# Aux_Lights_Daughter_REV2.net
KiCad netlist of a schematic drawn in Altium Designer
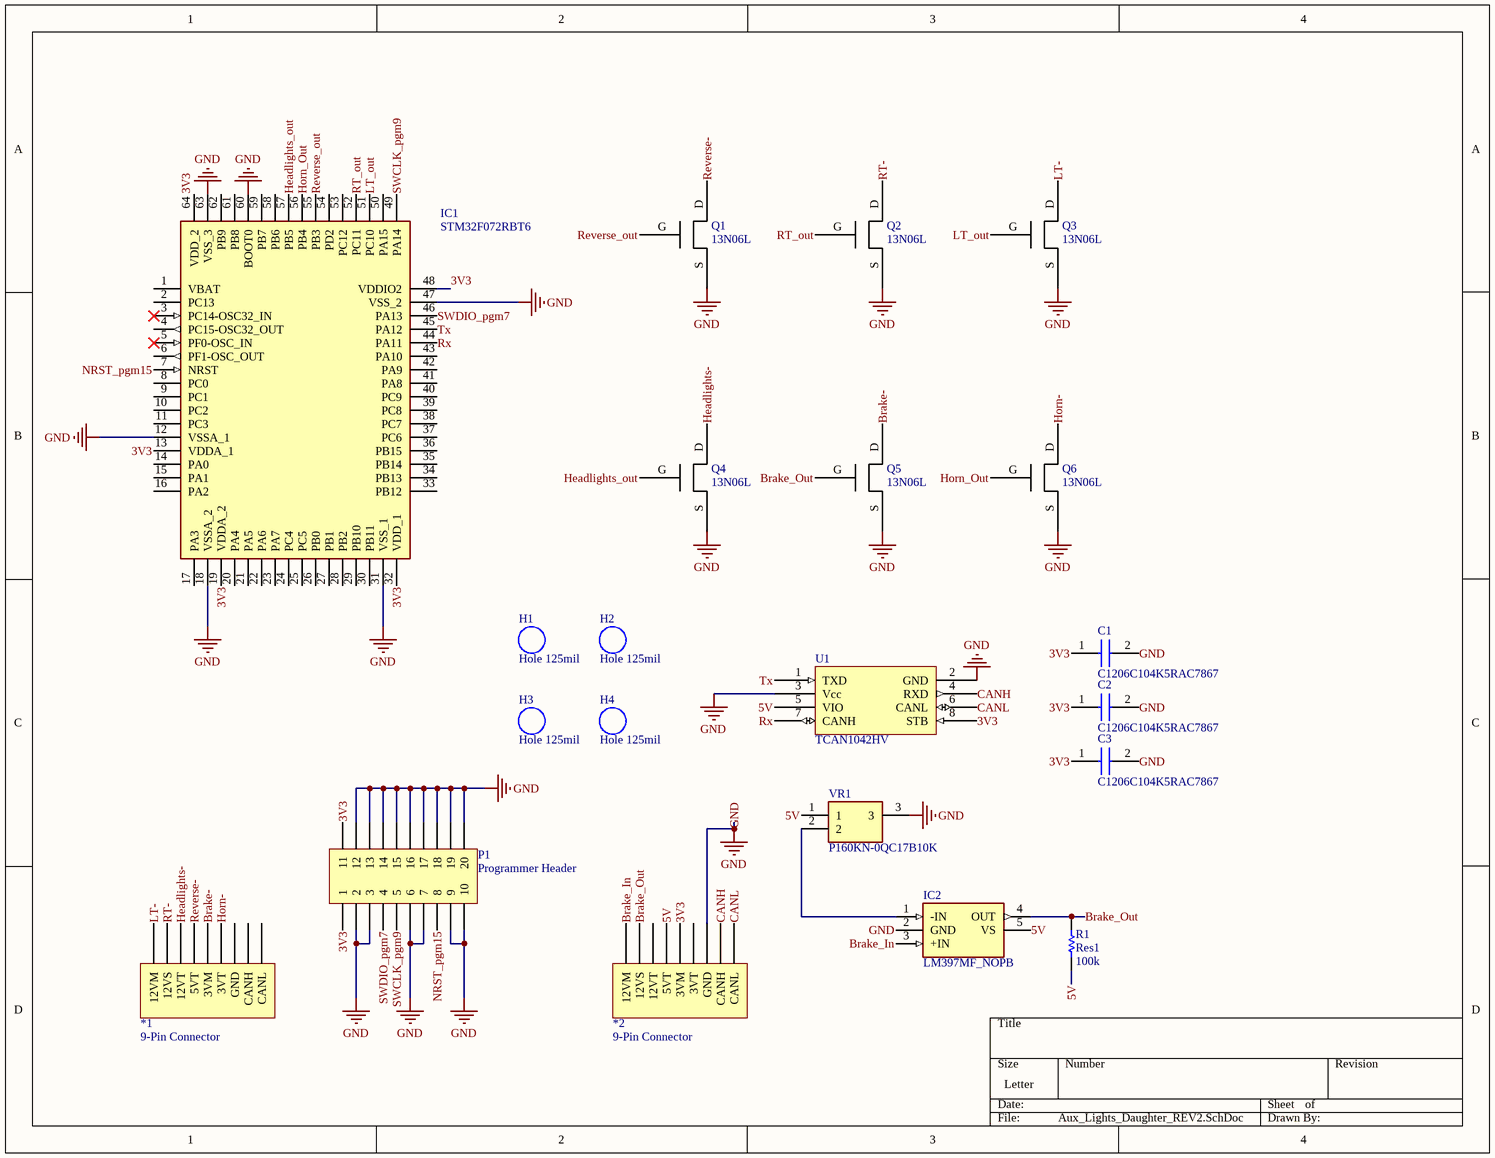
[diagram p0: Aux_Lights_Daughter_REV2.SchDoc]

(export (version "E")
  (design (tool "Eeschema 10.0.6"))
  (components
    (comp (ref "*1")
      (value "9-Pin Connector")
      (footprint "9-Pin")
      (libsource (lib "SolarGators") (part "9-Pin Connector"))
    )
    (comp (ref "*2")
      (value "9-Pin Connector")
      (footprint "9-Pin")
      (libsource (lib "SolarGators") (part "9-Pin Connector"))
    )
    (comp (ref "C1")
      (value "C1206C104K5RAC7867")
      (footprint "SamacSys:CAPC3216X110N")
      (description "Capacitor")
      (fields (field (name "MOUSER2 PART NUMBER") "80-C1206104K5RAC7867"))
      (libsource (lib "*") (part "C1206C104K5RAC7867"))
    )
    (comp (ref "C2")
      (value "C1206C104K5RAC7867")
      (footprint "SamacSys:CAPC3216X110N")
      (description "Capacitor")
      (fields (field (name "MOUSER2 PART NUMBER") "80-C1206104K5RAC7867"))
      (libsource (lib "*") (part "C1206C104K5RAC7867"))
    )
    (comp (ref "C3")
      (value "C1206C104K5RAC7867")
      (footprint "SamacSys:CAPC3216X110N")
      (description "Capacitor")
      (fields (field (name "MOUSER2 PART NUMBER") "80-C1206104K5RAC7867"))
      (libsource (lib "*") (part "C1206C104K5RAC7867"))
    )
    (comp (ref "H1")
      (value "Hole 125mil")
      (footprint "Hole 125mil")
      (libsource (lib "ECE LIB new") (part "Hole 125mil"))
    )
    (comp (ref "H2")
      (value "Hole 125mil")
      (footprint "Hole 125mil")
      (libsource (lib "ECE LIB new") (part "Hole 125mil"))
    )
    (comp (ref "H3")
      (value "Hole 125mil")
      (footprint "Hole 125mil")
      (libsource (lib "ECE LIB new") (part "Hole 125mil"))
    )
    (comp (ref "H4")
      (value "Hole 125mil")
      (footprint "Hole 125mil")
      (libsource (lib "ECE LIB new") (part "Hole 125mil"))
    )
    (comp (ref "IC1")
      (value "STM32F072RBT6")
      (footprint "QFP50P1200X1200X160-64N")
      (description "Integrated Circuit")
      (fields (field (name "MOUSER PART NUMBER") "511-STM32F072RBT6"))
      (libsource (lib "solargatorsproject") (part "STM32F072RBT6"))
    )
    (comp (ref "IC2")
      (value "LM397MF_NOPB")
      (footprint "SamacSys:SOT95P280X145-5N")
      (description "Integrated Circuit")
      (fields
        (field (name "MOUSER PART NUMBER") "926-LM397MF/NOPB")
        (field (name "MANUFACTURER_PART_NUMBER") "LM397MF/NOPB")
      )
      (libsource (lib "*") (part "LM397MF_NOPB"))
    )
    (comp (ref "P1")
      (value "Programmer Header")
      (footprint "HDR2X10_CEN")
      (description "Header, 10-Pin, Dual row")
      (fields (field (name "PUBLISHER") "Altium Limited"))
      (libsource (lib "Miscellaneous Connectors") (part "Header 10X2A"))
    )
    (comp (ref "Q1") (value "13N06L") (footprint "13N06L") (libsource (lib "SolarGators") (part "13N06L")))
    (comp (ref "Q2") (value "13N06L") (footprint "13N06L") (libsource (lib "SolarGators") (part "13N06L")))
    (comp (ref "Q3") (value "13N06L") (footprint "13N06L") (libsource (lib "SolarGators") (part "13N06L")))
    (comp (ref "Q4") (value "13N06L") (footprint "13N06L") (libsource (lib "SolarGators") (part "13N06L")))
    (comp (ref "Q5") (value "13N06L") (footprint "13N06L") (libsource (lib "SolarGators") (part "13N06L")))
    (comp (ref "Q6") (value "13N06L") (footprint "13N06L") (libsource (lib "SolarGators") (part "13N06L")))
    (comp (ref "R1")
      (value "Res1")
      (footprint "AXIAL-0.3")
      (description "Resistor")
      (fields (field (name "ALTIUM_VALUE") "100k") (field (name "PUBLISHER") "Altium Limited"))
      (libsource (lib "Miscellaneous Devices") (part "Res1"))
    )
    (comp (ref "U1")
      (value "TCAN1042HV")
      (footprint "CANIC")
      (description "TCAN1042Fault ProtectedCAN Transceiverwith CAN FD")
      (libsource (lib "Schlib1") (part "TCAN1042HV"))
    )
    (comp (ref "VR1")
      (value "P160KN-0QC17B10K")
      (footprint "POT inline wide")
      (description "Variable Resistor")
      (fields (field (name "MOUSER PART NUMBER") "858-P160KN-OQC17B10K"))
      (libsource (lib "*") (part "P160KN-0QC17B10K"))
    )
  )
  (nets
    (net (code "1") (name "/3V3") (class "Default")
      (node (ref "*2") (pin "5") (pinfunction "3VM_5") (pintype "passive"))
      (node (ref "C1") (pin "1") (pinfunction "1_1") (pintype "passive"))
      (node (ref "C2") (pin "1") (pinfunction "1_1") (pintype "passive"))
      (node (ref "C3") (pin "1") (pinfunction "1_1") (pintype "passive"))
      (node (ref "IC1") (pin "13") (pinfunction "VDDA_1_13") (pintype "power_in"))
      (node (ref "IC1") (pin "19") (pinfunction "VDDA_2_19") (pintype "power_in"))
      (node (ref "IC1") (pin "32") (pinfunction "VDD_1_32") (pintype "power_in"))
      (node (ref "IC1") (pin "48") (pinfunction "VDDIO2_48") (pintype "power_in"))
      (node (ref "IC1") (pin "64") (pinfunction "VDD_2_64") (pintype "power_in"))
      (node (ref "P1") (pin "1") (pinfunction "1_1") (pintype "passive"))
      (node (ref "P1") (pin "11") (pinfunction "11_11") (pintype "passive"))
      (node (ref "U1") (pin "8") (pinfunction "STB_8") (pintype "input"))
    )
    (net (code "2") (name "/5V") (class "Default")
      (node (ref "*2") (pin "4") (pinfunction "5VT_4") (pintype "passive"))
      (node (ref "IC2") (pin "5") (pinfunction "VS_5") (pintype "passive"))
      (node (ref "R1") (pin "1") (pinfunction "1_1") (pintype "passive"))
      (node (ref "U1") (pin "5") (pinfunction "VIO_5") (pintype "power_in"))
      (node (ref "VR1") (pin "1") (pinfunction "1_1") (pintype "passive"))
    )
    (net (code "3") (name "/Brake-") (class "Default")
      (node (ref "*1") (pin "5") (pinfunction "3VM_5") (pintype "passive"))
      (node (ref "Q5") (pin "D") (pinfunction "14_D") (pintype "passive"))
    )
    (net (code "4") (name "/Brake_In") (class "Default")
      (node (ref "*2") (pin "1") (pinfunction "12VM_1") (pintype "passive"))
      (node (ref "IC2") (pin "3") (pinfunction "+IN_3") (pintype "input"))
    )
    (net (code "5") (name "/Brake_Out") (class "Default")
      (node (ref "*2") (pin "2") (pinfunction "12VS_2") (pintype "passive"))
      (node (ref "IC2") (pin "4") (pinfunction "OUT_4") (pintype "output"))
      (node (ref "Q5") (pin "G") (pinfunction "13_G") (pintype "passive"))
      (node (ref "R1") (pin "2") (pinfunction "2_2") (pintype "passive"))
    )
    (net (code "6") (name "/CANH") (class "Default")
      (node (ref "*2") (pin "8") (pinfunction "CANH_8") (pintype "passive"))
      (node (ref "U1") (pin "4") (pinfunction "RXD_4") (pintype "output"))
    )
    (net (code "7") (name "/CANL") (class "Default")
      (node (ref "*2") (pin "9") (pinfunction "CANL_9") (pintype "passive"))
      (node (ref "U1") (pin "6") (pinfunction "CANL_6") (pintype "bidirectional"))
    )
    (net (code "8") (name "/Headlights-") (class "Default")
      (node (ref "*1") (pin "3") (pinfunction "12VT_3") (pintype "passive"))
      (node (ref "Q4") (pin "D") (pinfunction "14_D") (pintype "passive"))
    )
    (net (code "9") (name "/Headlights_out") (class "Default")
      (node (ref "IC1") (pin "57") (pinfunction "PB5_57") (pintype "passive"))
      (node (ref "Q4") (pin "G") (pinfunction "13_G") (pintype "passive"))
    )
    (net (code "10") (name "/Horn-") (class "Default")
      (node (ref "*1") (pin "6") (pinfunction "3VT_6") (pintype "passive"))
      (node (ref "Q6") (pin "D") (pinfunction "14_D") (pintype "passive"))
    )
    (net (code "11") (name "/Horn_Out") (class "Default")
      (node (ref "IC1") (pin "56") (pinfunction "PB4_56") (pintype "passive"))
      (node (ref "Q6") (pin "G") (pinfunction "13_G") (pintype "passive"))
    )
    (net (code "12") (name "/LT-") (class "Default")
      (node (ref "*1") (pin "1") (pinfunction "12VM_1") (pintype "passive"))
      (node (ref "Q3") (pin "D") (pinfunction "14_D") (pintype "passive"))
    )
    (net (code "13") (name "/LT_out") (class "Default")
      (node (ref "IC1") (pin "51") (pinfunction "PC10_51") (pintype "passive"))
      (node (ref "Q3") (pin "G") (pinfunction "13_G") (pintype "passive"))
    )
    (net (code "14") (name "/NRST_pgm15") (class "Default")
      (node (ref "IC1") (pin "7") (pinfunction "NRST_7") (pintype "input"))
      (node (ref "P1") (pin "8") (pinfunction "8_8") (pintype "passive"))
    )
    (net (code "15") (name "/RT-") (class "Default")
      (node (ref "*1") (pin "2") (pinfunction "12VS_2") (pintype "passive"))
      (node (ref "Q2") (pin "D") (pinfunction "14_D") (pintype "passive"))
    )
    (net (code "16") (name "/RT_out") (class "Default")
      (node (ref "IC1") (pin "52") (pinfunction "PC11_52") (pintype "passive"))
      (node (ref "Q2") (pin "G") (pinfunction "13_G") (pintype "passive"))
    )
    (net (code "17") (name "/Reverse-") (class "Default")
      (node (ref "*1") (pin "4") (pinfunction "5VT_4") (pintype "passive"))
      (node (ref "Q1") (pin "D") (pinfunction "14_D") (pintype "passive"))
    )
    (net (code "18") (name "/Reverse_out") (class "Default")
      (node (ref "IC1") (pin "55") (pinfunction "PB3_55") (pintype "passive"))
      (node (ref "Q1") (pin "G") (pinfunction "13_G") (pintype "passive"))
    )
    (net (code "19") (name "/Rx") (class "Default")
      (node (ref "IC1") (pin "44") (pinfunction "PA11_44") (pintype "passive"))
      (node (ref "U1") (pin "7") (pinfunction "CANH_7") (pintype "bidirectional"))
    )
    (net (code "20") (name "/SWCLK_pgm9") (class "Default")
      (node (ref "IC1") (pin "49") (pinfunction "PA14_49") (pintype "passive"))
      (node (ref "P1") (pin "5") (pinfunction "5_5") (pintype "passive"))
    )
    (net (code "21") (name "/SWDIO_pgm7") (class "Default")
      (node (ref "IC1") (pin "46") (pinfunction "PA13_46") (pintype "passive"))
      (node (ref "P1") (pin "4") (pinfunction "4_4") (pintype "passive"))
    )
    (net (code "22") (name "/Tx") (class "Default")
      (node (ref "IC1") (pin "45") (pinfunction "PA12_45") (pintype "passive"))
      (node (ref "U1") (pin "1") (pinfunction "TXD_1") (pintype "input"))
    )
    (net (code "23") (name "GND") (class "Default")
      (node (ref "*2") (pin "7") (pinfunction "GND_7") (pintype "passive"))
      (node (ref "C1") (pin "2") (pinfunction "2_2") (pintype "passive"))
      (node (ref "C2") (pin "2") (pinfunction "2_2") (pintype "passive"))
      (node (ref "C3") (pin "2") (pinfunction "2_2") (pintype "passive"))
      (node (ref "IC1") (pin "12") (pinfunction "VSSA_1_12") (pintype "power_in"))
      (node (ref "IC1") (pin "18") (pinfunction "VSSA_2_18") (pintype "power_in"))
      (node (ref "IC1") (pin "31") (pinfunction "VSS_1_31") (pintype "power_in"))
      (node (ref "IC1") (pin "47") (pinfunction "VSS_2_47") (pintype "power_in"))
      (node (ref "IC1") (pin "60") (pinfunction "BOOT0_60") (pintype "passive"))
      (node (ref "IC1") (pin "63") (pinfunction "VSS_3_63") (pintype "power_in"))
      (node (ref "IC2") (pin "2") (pinfunction "GND_2") (pintype "power_in"))
      (node (ref "P1") (pin "10") (pinfunction "10_10") (pintype "passive"))
      (node (ref "P1") (pin "12") (pinfunction "12_12") (pintype "passive"))
      (node (ref "P1") (pin "13") (pinfunction "13_13") (pintype "passive"))
      (node (ref "P1") (pin "14") (pinfunction "14_14") (pintype "passive"))
      (node (ref "P1") (pin "15") (pinfunction "15_15") (pintype "passive"))
      (node (ref "P1") (pin "16") (pinfunction "16_16") (pintype "passive"))
      (node (ref "P1") (pin "17") (pinfunction "17_17") (pintype "passive"))
      (node (ref "P1") (pin "18") (pinfunction "18_18") (pintype "passive"))
      (node (ref "P1") (pin "19") (pinfunction "19_19") (pintype "passive"))
      (node (ref "P1") (pin "2") (pinfunction "2_2") (pintype "passive"))
      (node (ref "P1") (pin "20") (pinfunction "20_20") (pintype "passive"))
      (node (ref "P1") (pin "3") (pinfunction "3_3") (pintype "passive"))
      (node (ref "P1") (pin "6") (pinfunction "6_6") (pintype "passive"))
      (node (ref "P1") (pin "7") (pinfunction "7_7") (pintype "passive"))
      (node (ref "P1") (pin "9") (pinfunction "9_9") (pintype "passive"))
      (node (ref "Q1") (pin "S") (pinfunction "15_S") (pintype "passive"))
      (node (ref "Q2") (pin "S") (pinfunction "15_S") (pintype "passive"))
      (node (ref "Q3") (pin "S") (pinfunction "15_S") (pintype "passive"))
      (node (ref "Q4") (pin "S") (pinfunction "15_S") (pintype "passive"))
      (node (ref "Q5") (pin "S") (pinfunction "15_S") (pintype "passive"))
      (node (ref "Q6") (pin "S") (pinfunction "15_S") (pintype "passive"))
      (node (ref "U1") (pin "2") (pinfunction "GND_2") (pintype "power_in"))
      (node (ref "U1") (pin "3") (pinfunction "Vcc_3") (pintype "power_in"))
      (node (ref "VR1") (pin "3") (pinfunction "3_3") (pintype "passive"))
    )
    (net (code "24") (name "Net-(IC2--IN)") (class "Default")
      (node (ref "IC2") (pin "1") (pinfunction "-IN_1") (pintype "input"))
      (node (ref "VR1") (pin "2") (pinfunction "2_2") (pintype "passive"))
    )
    (net (code "25") (name "unconnected-(*1-CANH-Pad8)") (class "Default")
      (node (ref "*1") (pin "8") (pinfunction "CANH_8") (pintype "passive"))
    )
    (net (code "26") (name "unconnected-(*1-CANL-Pad9)") (class "Default")
      (node (ref "*1") (pin "9") (pinfunction "CANL_9") (pintype "passive"))
    )
    (net (code "27") (name "unconnected-(*1-GND-Pad7)") (class "Default")
      (node (ref "*1") (pin "7") (pinfunction "GND_7") (pintype "passive"))
    )
    (net (code "28") (name "unconnected-(*2-3VT-Pad6)") (class "Default")
      (node (ref "*2") (pin "6") (pinfunction "3VT_6") (pintype "passive"))
    )
    (net (code "29") (name "unconnected-(*2-12VT-Pad3)") (class "Default")
      (node (ref "*2") (pin "3") (pinfunction "12VT_3") (pintype "passive"))
    )
    (net (code "30") (name "unconnected-(IC1-PA0-Pad14)") (class "Default")
      (node (ref "IC1") (pin "14") (pinfunction "PA0_14") (pintype "passive"))
    )
    (net (code "31") (name "unconnected-(IC1-PA1-Pad15)") (class "Default")
      (node (ref "IC1") (pin "15") (pinfunction "PA1_15") (pintype "passive"))
    )
    (net (code "32") (name "unconnected-(IC1-PA2-Pad16)") (class "Default")
      (node (ref "IC1") (pin "16") (pinfunction "PA2_16") (pintype "passive"))
    )
    (net (code "33") (name "unconnected-(IC1-PA3-Pad17)") (class "Default")
      (node (ref "IC1") (pin "17") (pinfunction "PA3_17") (pintype "passive"))
    )
    (net (code "34") (name "unconnected-(IC1-PA4-Pad20)") (class "Default")
      (node (ref "IC1") (pin "20") (pinfunction "PA4_20") (pintype "passive"))
    )
    (net (code "35") (name "unconnected-(IC1-PA5-Pad21)") (class "Default")
      (node (ref "IC1") (pin "21") (pinfunction "PA5_21") (pintype "passive"))
    )
    (net (code "36") (name "unconnected-(IC1-PA6-Pad22)") (class "Default")
      (node (ref "IC1") (pin "22") (pinfunction "PA6_22") (pintype "passive"))
    )
    (net (code "37") (name "unconnected-(IC1-PA7-Pad23)") (class "Default")
      (node (ref "IC1") (pin "23") (pinfunction "PA7_23") (pintype "passive"))
    )
    (net (code "38") (name "unconnected-(IC1-PA8-Pad41)") (class "Default")
      (node (ref "IC1") (pin "41") (pinfunction "PA8_41") (pintype "passive"))
    )
    (net (code "39") (name "unconnected-(IC1-PA9-Pad42)") (class "Default")
      (node (ref "IC1") (pin "42") (pinfunction "PA9_42") (pintype "passive"))
    )
    (net (code "40") (name "unconnected-(IC1-PA10-Pad43)") (class "Default")
      (node (ref "IC1") (pin "43") (pinfunction "PA10_43") (pintype "passive"))
    )
    (net (code "41") (name "unconnected-(IC1-PA15-Pad50)") (class "Default")
      (node (ref "IC1") (pin "50") (pinfunction "PA15_50") (pintype "passive"))
    )
    (net (code "42") (name "unconnected-(IC1-PB0-Pad26)") (class "Default")
      (node (ref "IC1") (pin "26") (pinfunction "PB0_26") (pintype "passive"))
    )
    (net (code "43") (name "unconnected-(IC1-PB1-Pad27)") (class "Default")
      (node (ref "IC1") (pin "27") (pinfunction "PB1_27") (pintype "passive"))
    )
    (net (code "44") (name "unconnected-(IC1-PB2-Pad28)") (class "Default")
      (node (ref "IC1") (pin "28") (pinfunction "PB2_28") (pintype "passive"))
    )
    (net (code "45") (name "unconnected-(IC1-PB6-Pad58)") (class "Default")
      (node (ref "IC1") (pin "58") (pinfunction "PB6_58") (pintype "passive"))
    )
    (net (code "46") (name "unconnected-(IC1-PB7-Pad59)") (class "Default")
      (node (ref "IC1") (pin "59") (pinfunction "PB7_59") (pintype "passive"))
    )
    (net (code "47") (name "unconnected-(IC1-PB8-Pad61)") (class "Default")
      (node (ref "IC1") (pin "61") (pinfunction "PB8_61") (pintype "passive"))
    )
    (net (code "48") (name "unconnected-(IC1-PB9-Pad62)") (class "Default")
      (node (ref "IC1") (pin "62") (pinfunction "PB9_62") (pintype "passive"))
    )
    (net (code "49") (name "unconnected-(IC1-PB10-Pad29)") (class "Default")
      (node (ref "IC1") (pin "29") (pinfunction "PB10_29") (pintype "passive"))
    )
    (net (code "50") (name "unconnected-(IC1-PB11-Pad30)") (class "Default")
      (node (ref "IC1") (pin "30") (pinfunction "PB11_30") (pintype "passive"))
    )
    (net (code "51") (name "unconnected-(IC1-PB12-Pad33)") (class "Default")
      (node (ref "IC1") (pin "33") (pinfunction "PB12_33") (pintype "passive"))
    )
    (net (code "52") (name "unconnected-(IC1-PB13-Pad34)") (class "Default")
      (node (ref "IC1") (pin "34") (pinfunction "PB13_34") (pintype "passive"))
    )
    (net (code "53") (name "unconnected-(IC1-PB14-Pad35)") (class "Default")
      (node (ref "IC1") (pin "35") (pinfunction "PB14_35") (pintype "passive"))
    )
    (net (code "54") (name "unconnected-(IC1-PB15-Pad36)") (class "Default")
      (node (ref "IC1") (pin "36") (pinfunction "PB15_36") (pintype "passive"))
    )
    (net (code "55") (name "unconnected-(IC1-PC0-Pad8)") (class "Default")
      (node (ref "IC1") (pin "8") (pinfunction "PC0_8") (pintype "passive"))
    )
    (net (code "56") (name "unconnected-(IC1-PC1-Pad9)") (class "Default")
      (node (ref "IC1") (pin "9") (pinfunction "PC1_9") (pintype "passive"))
    )
    (net (code "57") (name "unconnected-(IC1-PC2-Pad10)") (class "Default")
      (node (ref "IC1") (pin "10") (pinfunction "PC2_10") (pintype "passive"))
    )
    (net (code "58") (name "unconnected-(IC1-PC3-Pad11)") (class "Default")
      (node (ref "IC1") (pin "11") (pinfunction "PC3_11") (pintype "passive"))
    )
    (net (code "59") (name "unconnected-(IC1-PC4-Pad24)") (class "Default")
      (node (ref "IC1") (pin "24") (pinfunction "PC4_24") (pintype "passive"))
    )
    (net (code "60") (name "unconnected-(IC1-PC5-Pad25)") (class "Default")
      (node (ref "IC1") (pin "25") (pinfunction "PC5_25") (pintype "passive"))
    )
    (net (code "61") (name "unconnected-(IC1-PC6-Pad37)") (class "Default")
      (node (ref "IC1") (pin "37") (pinfunction "PC6_37") (pintype "passive"))
    )
    (net (code "62") (name "unconnected-(IC1-PC7-Pad38)") (class "Default")
      (node (ref "IC1") (pin "38") (pinfunction "PC7_38") (pintype "passive"))
    )
    (net (code "63") (name "unconnected-(IC1-PC8-Pad39)") (class "Default")
      (node (ref "IC1") (pin "39") (pinfunction "PC8_39") (pintype "passive"))
    )
    (net (code "64") (name "unconnected-(IC1-PC9-Pad40)") (class "Default")
      (node (ref "IC1") (pin "40") (pinfunction "PC9_40") (pintype "passive"))
    )
    (net (code "65") (name "unconnected-(IC1-PC12-Pad53)") (class "Default")
      (node (ref "IC1") (pin "53") (pinfunction "PC12_53") (pintype "passive"))
    )
    (net (code "66") (name "unconnected-(IC1-PC13-Pad2)") (class "Default")
      (node (ref "IC1") (pin "2") (pinfunction "PC13_2") (pintype "passive"))
    )
    (net (code "67") (name "unconnected-(IC1-PC14-OSC32_IN-Pad3)") (class "Default")
      (node (ref "IC1") (pin "3") (pinfunction "PC14-OSC32_IN_3") (pintype "input+no_connect"))
    )
    (net (code "68") (name "unconnected-(IC1-PC15-OSC32_OUT-Pad4)") (class "Default")
      (node (ref "IC1") (pin "4") (pinfunction "PC15-OSC32_OUT_4") (pintype "output"))
    )
    (net (code "69") (name "unconnected-(IC1-PD2-Pad54)") (class "Default")
      (node (ref "IC1") (pin "54") (pinfunction "PD2_54") (pintype "passive"))
    )
    (net (code "70") (name "unconnected-(IC1-PF0-OSC_IN-Pad5)") (class "Default")
      (node (ref "IC1") (pin "5") (pinfunction "PF0-OSC_IN_5") (pintype "input+no_connect"))
    )
    (net (code "71") (name "unconnected-(IC1-PF1-OSC_OUT-Pad6)") (class "Default")
      (node (ref "IC1") (pin "6") (pinfunction "PF1-OSC_OUT_6") (pintype "output"))
    )
    (net (code "72") (name "unconnected-(IC1-VBAT-Pad1)") (class "Default")
      (node (ref "IC1") (pin "1") (pinfunction "VBAT_1") (pintype "passive"))
    )
  )
)
